# THC-schematicRevE.net
KiCad netlist of a schematic drawn in EAGLE
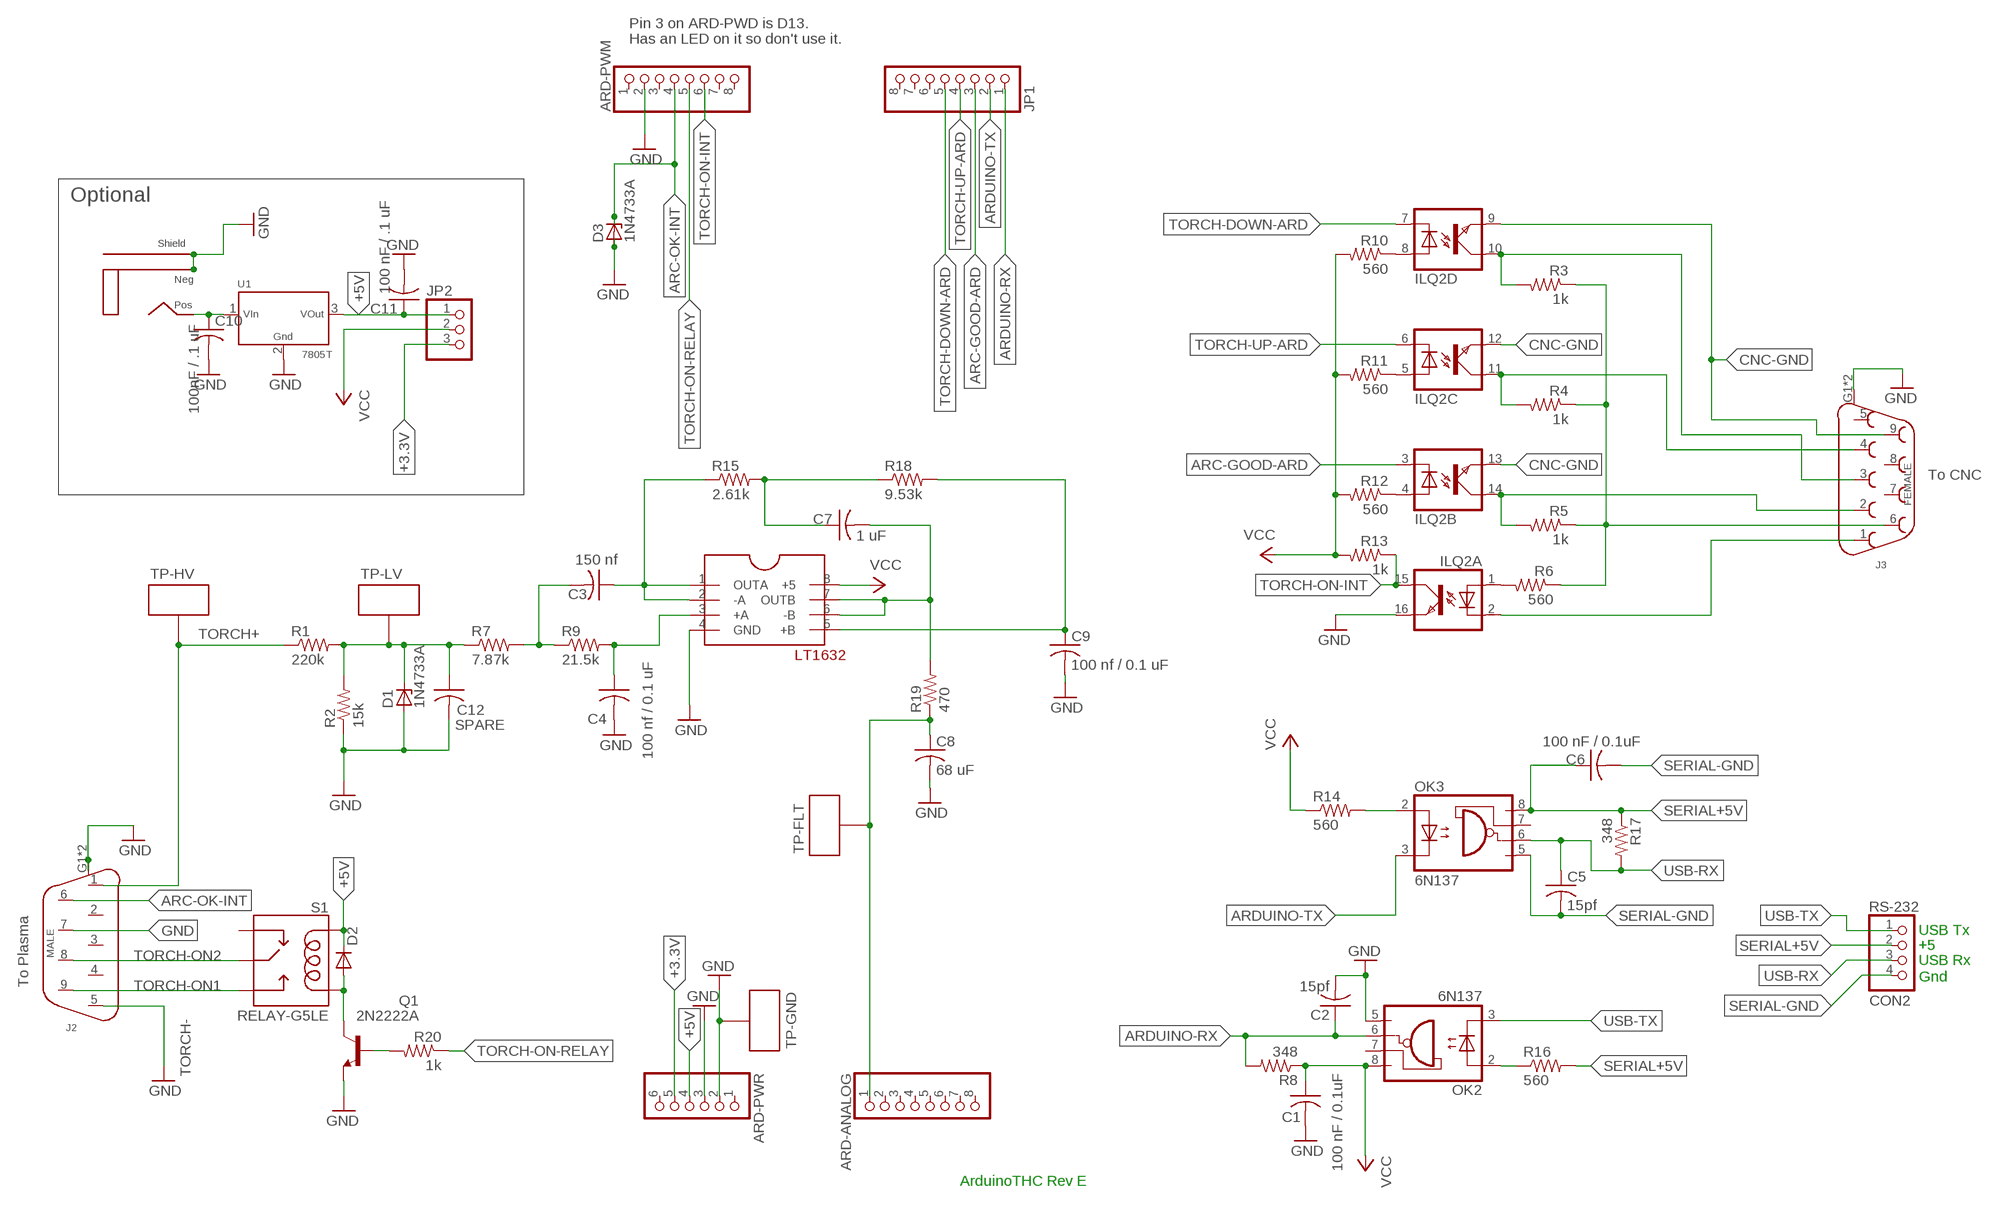
[diagram p0: schematic, sheet 1]

(export (version "E")
  (design (tool "Eeschema 10.0.6"))
  (components
    (comp (ref "ARD-ANALOG")
      (value "PINHD-1X8")
      (footprint "eagle-import:1X08")
      (libsource (lib "eagle-import") (part "PINHD-1X8"))
    )
    (comp (ref "ARD-PWM")
      (value "PINHD-1X8")
      (footprint "eagle-import:1X08")
      (libsource (lib "eagle-import") (part "PINHD-1X8"))
    )
    (comp (ref "ARD-PWR")
      (value "PINHD-1X6")
      (footprint "eagle-import:1X06")
      (libsource (lib "eagle-import") (part "PINHD-1X6"))
    )
    (comp (ref "C1")
      (value "100 nF / 0.1uF")
      (footprint "eagle-import:C025-025X050")
      (libsource (lib "eagle-import") (part "C-US025-025X050"))
    )
    (comp (ref "C2")
      (value "15pf")
      (footprint "eagle-import:C025-025X050")
      (libsource (lib "eagle-import") (part "C-US025-025X050"))
    )
    (comp (ref "C3")
      (value "150 nf")
      (footprint "eagle-import:C025-025X050")
      (libsource (lib "eagle-import") (part "C-US025-025X050"))
    )
    (comp (ref "C4")
      (value "100 nf / 0.1 uF")
      (footprint "eagle-import:C025-025X050")
      (libsource (lib "eagle-import") (part "C-US025-025X050"))
    )
    (comp (ref "C5")
      (value "15pf")
      (footprint "eagle-import:C025-025X050")
      (libsource (lib "eagle-import") (part "C-US025-025X050"))
    )
    (comp (ref "C6")
      (value "100 nF / 0.1uF")
      (footprint "eagle-import:C025-025X050")
      (libsource (lib "eagle-import") (part "C-US025-025X050"))
    )
    (comp (ref "C7")
      (value "1 uF")
      (footprint "eagle-import:C025-025X050")
      (libsource (lib "eagle-import") (part "C-US025-025X050"))
    )
    (comp (ref "C8")
      (value "68 uF")
      (footprint "eagle-import:C025-025X050")
      (libsource (lib "eagle-import") (part "C-US025-025X050"))
    )
    (comp (ref "C9")
      (value "100 nf / 0.1 uF")
      (footprint "eagle-import:C025-025X050")
      (libsource (lib "eagle-import") (part "C-US025-025X050"))
    )
    (comp (ref "C10")
      (value "100nF / .1 uF")
      (footprint "eagle-import:C025-025X050")
      (libsource (lib "eagle-import") (part "C-US025-025X050"))
    )
    (comp (ref "C11")
      (value "100 nF / .1 uF")
      (footprint "eagle-import:C025-025X050")
      (libsource (lib "eagle-import") (part "C-US025-025X050"))
    )
    (comp (ref "C12")
      (value "SPARE")
      (footprint "eagle-import:C025-025X050")
      (libsource (lib "eagle-import") (part "C-US025-025X050"))
    )
    (comp (ref "D1")
      (value "1N4733A")
      (footprint "eagle-import:DO41Z10")
      (libsource (lib "eagle-import") (part "ZPY"))
    )
    (comp (ref "D2")
      (value "1N4001")
      (footprint "eagle-import:DO-204AL")
      (libsource (lib "eagle-import") (part "1N4001"))
    )
    (comp (ref "D3")
      (value "1N4733A")
      (footprint "eagle-import:DO41Z10")
      (libsource (lib "eagle-import") (part "ZPY"))
    )
    (comp (ref "ILQ2")
      (value "ILQ1")
      (footprint "eagle-import:DIL16")
      (fields (field (name "MF") "VISHAY/TELEFUNKEN"))
      (libsource (lib "eagle-import") (part "ILQ1"))
    )
    (comp (ref "J1")
      (value "2.1MM-PLUG-PCB-MNT")
      (footprint "eagle-import:2.1MM-PLUG")
      (libsource (lib "eagle-import") (part "2.1MM-PLUG-PCB-MNT"))
    )
    (comp (ref "J2")
      (value "DB9-MALE")
      (footprint "eagle-import:DB9M-RIGHT-ANGLE")
      (libsource (lib "eagle-import") (part "DB9-MALE"))
    )
    (comp (ref "J3")
      (value "DB9-FEMALE")
      (footprint "eagle-import:DB9F-RIGHT-ANGLE")
      (libsource (lib "eagle-import") (part "DB9-FEMALE"))
    )
    (comp (ref "JP1")
      (value "PINHD-1X8")
      (footprint "eagle-import:1X08")
      (libsource (lib "eagle-import") (part "PINHD-1X8"))
    )
    (comp (ref "JP2")
      (value "PINHD-1X3")
      (footprint "eagle-import:1X03")
      (libsource (lib "eagle-import") (part "PINHD-1X3"))
    )
    (comp (ref "OK2")
      (value "6N137")
      (footprint "eagle-import:DIL08")
      (libsource (lib "eagle-import") (part "6N137"))
    )
    (comp (ref "OK3")
      (value "6N137")
      (footprint "eagle-import:DIL08")
      (libsource (lib "eagle-import") (part "6N137"))
    )
    (comp (ref "Q1")
      (value "2N2222A")
      (footprint "eagle-import:TO18")
      (libsource (lib "eagle-import") (part "2N2222A"))
    )
    (comp (ref "R1")
      (value "220k")
      (footprint "eagle-import:0207_7")
      (libsource (lib "eagle-import") (part "R-US_0207/7"))
    )
    (comp (ref "R2")
      (value "15k")
      (footprint "eagle-import:0207_7")
      (libsource (lib "eagle-import") (part "R-US_0207/7"))
    )
    (comp (ref "R3")
      (value "1k")
      (footprint "eagle-import:0207_7")
      (libsource (lib "eagle-import") (part "R-US_0207/7"))
    )
    (comp (ref "R4")
      (value "1k")
      (footprint "eagle-import:0207_7")
      (libsource (lib "eagle-import") (part "R-US_0207/7"))
    )
    (comp (ref "R5")
      (value "1k")
      (footprint "eagle-import:0207_7")
      (libsource (lib "eagle-import") (part "R-US_0207/7"))
    )
    (comp (ref "R6")
      (value "560")
      (footprint "eagle-import:0207_7")
      (libsource (lib "eagle-import") (part "R-US_0207/7"))
    )
    (comp (ref "R7")
      (value "7.87k")
      (footprint "eagle-import:0207_7")
      (libsource (lib "eagle-import") (part "R-US_0207/7"))
    )
    (comp (ref "R8")
      (value "348")
      (footprint "eagle-import:0207_7")
      (libsource (lib "eagle-import") (part "R-US_0207/7"))
    )
    (comp (ref "R9")
      (value "21.5k")
      (footprint "eagle-import:0207_7")
      (libsource (lib "eagle-import") (part "R-US_0207/7"))
    )
    (comp (ref "R10")
      (value "560")
      (footprint "eagle-import:0207_7")
      (libsource (lib "eagle-import") (part "R-US_0207/7"))
    )
    (comp (ref "R11")
      (value "560")
      (footprint "eagle-import:0207_7")
      (libsource (lib "eagle-import") (part "R-US_0207/7"))
    )
    (comp (ref "R12")
      (value "560")
      (footprint "eagle-import:0207_7")
      (libsource (lib "eagle-import") (part "R-US_0207/7"))
    )
    (comp (ref "R13")
      (value "1k")
      (footprint "eagle-import:0207_7")
      (libsource (lib "eagle-import") (part "R-US_0207/7"))
    )
    (comp (ref "R14")
      (value "560")
      (footprint "eagle-import:0207_7")
      (libsource (lib "eagle-import") (part "R-US_0207/7"))
    )
    (comp (ref "R15")
      (value "2.61k")
      (footprint "eagle-import:0207_7")
      (libsource (lib "eagle-import") (part "R-US_0207/7"))
    )
    (comp (ref "R16")
      (value "560")
      (footprint "eagle-import:0207_7")
      (libsource (lib "eagle-import") (part "R-US_0207/7"))
    )
    (comp (ref "R17")
      (value "348")
      (footprint "eagle-import:0207_7")
      (libsource (lib "eagle-import") (part "R-US_0207/7"))
    )
    (comp (ref "R18")
      (value "9.53k")
      (footprint "eagle-import:0207_7")
      (libsource (lib "eagle-import") (part "R-US_0207/7"))
    )
    (comp (ref "R19")
      (value "470")
      (footprint "eagle-import:0207_7")
      (libsource (lib "eagle-import") (part "R-US_0207/7"))
    )
    (comp (ref "R20")
      (value "1k")
      (footprint "eagle-import:0207_7")
      (libsource (lib "eagle-import") (part "R-US_0207/7"))
    )
    (comp (ref "RS-232")
      (value "CON2")
      (footprint "eagle-import:1X04")
      (libsource (lib "eagle-import") (part "PINHD-1X4"))
    )
    (comp (ref "S1")
      (value "RELAY-G5LE")
      (footprint "eagle-import:RELAY-G5LE")
      (libsource (lib "eagle-import") (part "RELAY-G5LE"))
    )
    (comp (ref "TP-FLT")
      (value "TEST-POINT-.040-HOLE")
      (footprint "eagle-import:TP.040")
      (libsource (lib "eagle-import") (part "TEST-POINT-.040-HOLE"))
    )
    (comp (ref "TP-GND")
      (value "TEST-POINT-.040-HOLE")
      (footprint "eagle-import:TP.040")
      (libsource (lib "eagle-import") (part "TEST-POINT-.040-HOLE"))
    )
    (comp (ref "TP-HV")
      (value "TEST-POINT-.040-HOLE")
      (footprint "eagle-import:TP.040")
      (libsource (lib "eagle-import") (part "TEST-POINT-.040-HOLE"))
    )
    (comp (ref "TP-LV")
      (value "TEST-POINT-.040-HOLE")
      (footprint "eagle-import:TP.040")
      (libsource (lib "eagle-import") (part "TEST-POINT-.040-HOLE"))
    )
    (comp (ref "U$1")
      (value "LT1632")
      (footprint "eagle-import:DIP08")
      (libsource (lib "eagle-import") (part "LT1632"))
    )
    (comp (ref "U1")
      (value "7805T")
      (footprint "eagle-import:TO-220-3")
      (libsource (lib "eagle-import") (part "7805T"))
    )
  )
  (nets
    (net (code "1") (name "+3.3V") (class "Default")
      (node (ref "ARD-PWR") (pin "5") (pinfunction "5_5") (pintype "passive"))
      (node (ref "JP2") (pin "3") (pinfunction "3_3") (pintype "passive"))
    )
    (net (code "2") (name "+5V") (class "Default")
      (node (ref "ARD-PWR") (pin "4") (pinfunction "4_4") (pintype "passive"))
      (node (ref "C11") (pin "1") (pinfunction "1_1") (pintype "passive"))
      (node (ref "D2") (pin "C") (pinfunction "C_C") (pintype "passive"))
      (node (ref "JP2") (pin "1") (pinfunction "1_1") (pintype "passive"))
      (node (ref "S1") (pin "P$5-COIL") (pinfunction "COIL-2_P$5-COIL") (pintype "bidirectional"))
      (node (ref "U1") (pin "3") (pinfunction "VOUT_3") (pintype "bidirectional"))
    )
    (net (code "3") (name "/TORCH-ON1") (class "Default")
      (node (ref "J2") (pin "9") (pinfunction "P$9_9") (pintype "bidirectional"))
      (node (ref "S1") (pin "P$4-NO") (pinfunction "NO_P$4-NO") (pintype "bidirectional"))
    )
    (net (code "4") (name "/TORCH-ON2") (class "Default")
      (node (ref "J2") (pin "8") (pinfunction "P$8_8") (pintype "bidirectional"))
      (node (ref "S1") (pin "P$1-COMMON") (pinfunction "COM_P$1-COMMON") (pintype "bidirectional"))
    )
    (net (code "5") (name "ARC-GOOD-ARD") (class "Default")
      (node (ref "ILQ2") (pin "3") (pinfunction "C_3") (pintype "passive"))
      (node (ref "JP1") (pin "3") (pinfunction "3_3") (pintype "passive"))
    )
    (net (code "6") (name "ARC-OK-INT") (class "Default")
      (node (ref "ARD-PWM") (pin "4") (pinfunction "4_4") (pintype "passive"))
      (node (ref "D3") (pin "C") (pinfunction "C_C") (pintype "passive"))
      (node (ref "J2") (pin "6") (pinfunction "P$6_6") (pintype "bidirectional"))
    )
    (net (code "7") (name "ARDUINO-RX") (class "Default")
      (node (ref "C2") (pin "1") (pinfunction "1_1") (pintype "passive"))
      (node (ref "JP1") (pin "1") (pinfunction "1_1") (pintype "passive"))
      (node (ref "OK2") (pin "6") (pinfunction "VO_6") (pintype "passive"))
      (node (ref "R8") (pin "2") (pinfunction "2_2") (pintype "passive"))
    )
    (net (code "8") (name "ARDUINO-TX") (class "Default")
      (node (ref "JP1") (pin "2") (pinfunction "2_2") (pintype "passive"))
      (node (ref "OK3") (pin "3") (pinfunction "C_3") (pintype "passive"))
    )
    (net (code "9") (name "CNC-GND") (class "Default")
      (node (ref "ILQ2") (pin "12") (pinfunction "EMIT_12") (pintype "passive"))
      (node (ref "ILQ2") (pin "13") (pinfunction "EMIT_13") (pintype "passive"))
      (node (ref "ILQ2") (pin "9") (pinfunction "EMIT_9") (pintype "passive"))
      (node (ref "J3") (pin "9") (pinfunction "P$9_9") (pintype "bidirectional"))
    )
    (net (code "10") (name "GND") (class "Default")
      (node (ref "ARD-PWM") (pin "2") (pinfunction "2_2") (pintype "passive"))
      (node (ref "ARD-PWR") (pin "2") (pinfunction "2_2") (pintype "passive"))
      (node (ref "ARD-PWR") (pin "3") (pinfunction "3_3") (pintype "passive"))
      (node (ref "C1") (pin "2") (pinfunction "2_2") (pintype "passive"))
      (node (ref "C10") (pin "2") (pinfunction "2_2") (pintype "passive"))
      (node (ref "C11") (pin "2") (pinfunction "2_2") (pintype "passive"))
      (node (ref "C12") (pin "2") (pinfunction "2_2") (pintype "passive"))
      (node (ref "C2") (pin "2") (pinfunction "2_2") (pintype "passive"))
      (node (ref "C4") (pin "2") (pinfunction "2_2") (pintype "passive"))
      (node (ref "C8") (pin "2") (pinfunction "2_2") (pintype "passive"))
      (node (ref "C9") (pin "2") (pinfunction "2_2") (pintype "passive"))
      (node (ref "D1") (pin "A") (pinfunction "A_A") (pintype "passive"))
      (node (ref "D3") (pin "A") (pinfunction "A_A") (pintype "passive"))
      (node (ref "ILQ2") (pin "16") (pinfunction "EMIT_16") (pintype "passive"))
      (node (ref "J1") (pin "P$NEG") (pinfunction "P$NEG_P$NEG") (pintype "bidirectional"))
      (node (ref "J1") (pin "P$SHLD") (pinfunction "P$SHLD_P$SHLD") (pintype "bidirectional"))
      (node (ref "J2") (pin "5") (pinfunction "P$5_5") (pintype "bidirectional"))
      (node (ref "J2") (pin "7") (pinfunction "P$7_7") (pintype "bidirectional"))
      (node (ref "J2") (pin "G1") (pinfunction "P$SHLD_G1") (pintype "bidirectional"))
      (node (ref "J2") (pin "G2") (pinfunction "P$SHLD_G2") (pintype "bidirectional"))
      (node (ref "J3") (pin "G1") (pinfunction "P$SHLD_G1") (pintype "bidirectional"))
      (node (ref "J3") (pin "G2") (pinfunction "P$SHLD_G2") (pintype "bidirectional"))
      (node (ref "OK2") (pin "5") (pinfunction "GND_5") (pintype "passive"))
      (node (ref "Q1") (pin "1") (pinfunction "E_1") (pintype "passive"))
      (node (ref "R2") (pin "1") (pinfunction "1_1") (pintype "passive"))
      (node (ref "TP-GND") (pin "P$1") (pinfunction "P$1_P$1") (pintype "bidirectional"))
      (node (ref "U$1") (pin "4") (pinfunction "GND_4") (pintype "bidirectional"))
      (node (ref "U1") (pin "2") (pinfunction "GND_2") (pintype "bidirectional"))
    )
    (net (code "11") (name "Net-(ARD-ANALOG-Pad1)") (class "Default")
      (node (ref "ARD-ANALOG") (pin "1") (pinfunction "1_1") (pintype "passive"))
      (node (ref "C8") (pin "1") (pinfunction "1_1") (pintype "passive"))
      (node (ref "R19") (pin "1") (pinfunction "1_1") (pintype "passive"))
      (node (ref "TP-FLT") (pin "P$1") (pinfunction "P$1_P$1") (pintype "bidirectional"))
    )
    (net (code "12") (name "Net-(C3-Pad2)") (class "Default")
      (node (ref "C3") (pin "2") (pinfunction "2_2") (pintype "passive"))
      (node (ref "R7") (pin "2") (pinfunction "2_2") (pintype "passive"))
      (node (ref "R9") (pin "1") (pinfunction "1_1") (pintype "passive"))
    )
    (net (code "13") (name "Net-(C7-Pad1)") (class "Default")
      (node (ref "C7") (pin "1") (pinfunction "1_1") (pintype "passive"))
      (node (ref "R15") (pin "2") (pinfunction "2_2") (pintype "passive"))
      (node (ref "R18") (pin "1") (pinfunction "1_1") (pintype "passive"))
    )
    (net (code "14") (name "Net-(C12-Pad1)") (class "Default")
      (node (ref "C12") (pin "1") (pinfunction "1_1") (pintype "passive"))
      (node (ref "D1") (pin "C") (pinfunction "C_C") (pintype "passive"))
      (node (ref "R1") (pin "2") (pinfunction "2_2") (pintype "passive"))
      (node (ref "R2") (pin "2") (pinfunction "2_2") (pintype "passive"))
      (node (ref "R7") (pin "1") (pinfunction "1_1") (pintype "passive"))
      (node (ref "TP-LV") (pin "P$1") (pinfunction "P$1_P$1") (pintype "bidirectional"))
    )
    (net (code "15") (name "Net-(ILQ2A-A)") (class "Default")
      (node (ref "ILQ2") (pin "1") (pinfunction "A_1") (pintype "passive"))
      (node (ref "R6") (pin "2") (pinfunction "2_2") (pintype "passive"))
    )
    (net (code "16") (name "Net-(ILQ2A-C)") (class "Default")
      (node (ref "ILQ2") (pin "2") (pinfunction "C_2") (pintype "passive"))
      (node (ref "J3") (pin "1") (pinfunction "P$1_1") (pintype "bidirectional"))
    )
    (net (code "17") (name "Net-(ILQ2B-A)") (class "Default")
      (node (ref "ILQ2") (pin "4") (pinfunction "A_4") (pintype "passive"))
      (node (ref "R12") (pin "1") (pinfunction "1_1") (pintype "passive"))
    )
    (net (code "18") (name "Net-(ILQ2B-COL)") (class "Default")
      (node (ref "ILQ2") (pin "14") (pinfunction "COL_14") (pintype "passive"))
      (node (ref "J3") (pin "2") (pinfunction "P$2_2") (pintype "bidirectional"))
      (node (ref "R5") (pin "2") (pinfunction "2_2") (pintype "passive"))
    )
    (net (code "19") (name "Net-(ILQ2C-A)") (class "Default")
      (node (ref "ILQ2") (pin "5") (pinfunction "A_5") (pintype "passive"))
      (node (ref "R11") (pin "1") (pinfunction "1_1") (pintype "passive"))
    )
    (net (code "20") (name "Net-(ILQ2C-COL)") (class "Default")
      (node (ref "ILQ2") (pin "11") (pinfunction "COL_11") (pintype "passive"))
      (node (ref "J3") (pin "4") (pinfunction "P$4_4") (pintype "bidirectional"))
      (node (ref "R4") (pin "2") (pinfunction "2_2") (pintype "passive"))
    )
    (net (code "21") (name "Net-(ILQ2D-A)") (class "Default")
      (node (ref "ILQ2") (pin "8") (pinfunction "A_8") (pintype "passive"))
      (node (ref "R10") (pin "1") (pinfunction "1_1") (pintype "passive"))
    )
    (net (code "22") (name "Net-(ILQ2D-COL)") (class "Default")
      (node (ref "ILQ2") (pin "10") (pinfunction "COL_10") (pintype "passive"))
      (node (ref "J3") (pin "3") (pinfunction "P$3_3") (pintype "bidirectional"))
      (node (ref "R3") (pin "2") (pinfunction "2_2") (pintype "passive"))
    )
    (net (code "23") (name "Net-(J2-P$1)") (class "Default")
      (node (ref "J2") (pin "1") (pinfunction "P$1_1") (pintype "bidirectional"))
      (node (ref "R1") (pin "1") (pinfunction "1_1") (pintype "passive"))
      (node (ref "TP-HV") (pin "P$1") (pinfunction "P$1_P$1") (pintype "bidirectional"))
    )
    (net (code "24") (name "Net-(J3-P$6)") (class "Default")
      (node (ref "J3") (pin "6") (pinfunction "P$6_6") (pintype "bidirectional"))
      (node (ref "R3") (pin "1") (pinfunction "1_1") (pintype "passive"))
      (node (ref "R4") (pin "1") (pinfunction "1_1") (pintype "passive"))
      (node (ref "R5") (pin "1") (pinfunction "1_1") (pintype "passive"))
      (node (ref "R6") (pin "1") (pinfunction "1_1") (pintype "passive"))
    )
    (net (code "25") (name "Net-(OK2-A)") (class "Default")
      (node (ref "OK2") (pin "2") (pinfunction "A_2") (pintype "passive"))
      (node (ref "R16") (pin "1") (pinfunction "1_1") (pintype "passive"))
    )
    (net (code "26") (name "Net-(OK3-A)") (class "Default")
      (node (ref "OK3") (pin "2") (pinfunction "A_2") (pintype "passive"))
      (node (ref "R14") (pin "2") (pinfunction "2_2") (pintype "passive"))
    )
    (net (code "27") (name "Net-(Q1-B)") (class "Default")
      (node (ref "Q1") (pin "2") (pinfunction "B_2") (pintype "passive"))
      (node (ref "R20") (pin "2") (pinfunction "2_2") (pintype "passive"))
    )
    (net (code "28") (name "Net-(Q1-C)") (class "Default")
      (node (ref "D2") (pin "A") (pinfunction "A_A") (pintype "passive"))
      (node (ref "Q1") (pin "3") (pinfunction "C_3") (pintype "passive"))
      (node (ref "S1") (pin "P$2-COIL") (pinfunction "COIL-1_P$2-COIL") (pintype "bidirectional"))
    )
    (net (code "29") (name "Net-(U$1-+A)") (class "Default")
      (node (ref "C4") (pin "1") (pinfunction "1_1") (pintype "passive"))
      (node (ref "R9") (pin "2") (pinfunction "2_2") (pintype "passive"))
      (node (ref "U$1") (pin "3") (pinfunction "+A_3") (pintype "bidirectional"))
    )
    (net (code "30") (name "Net-(U$1-+B)") (class "Default")
      (node (ref "C9") (pin "1") (pinfunction "1_1") (pintype "passive"))
      (node (ref "R18") (pin "2") (pinfunction "2_2") (pintype "passive"))
      (node (ref "U$1") (pin "5") (pinfunction "+B_5") (pintype "bidirectional"))
    )
    (net (code "31") (name "Net-(U$1--A)") (class "Default")
      (node (ref "C3") (pin "1") (pinfunction "1_1") (pintype "passive"))
      (node (ref "R15") (pin "1") (pinfunction "1_1") (pintype "passive"))
      (node (ref "U$1") (pin "1") (pinfunction "OUTA_1") (pintype "bidirectional"))
      (node (ref "U$1") (pin "2") (pinfunction "-A_2") (pintype "bidirectional"))
    )
    (net (code "32") (name "Net-(U$1--B)") (class "Default")
      (node (ref "C7") (pin "2") (pinfunction "2_2") (pintype "passive"))
      (node (ref "R19") (pin "2") (pinfunction "2_2") (pintype "passive"))
      (node (ref "U$1") (pin "6") (pinfunction "-B_6") (pintype "bidirectional"))
      (node (ref "U$1") (pin "7") (pinfunction "OUTB_7") (pintype "bidirectional"))
    )
    (net (code "33") (name "Net-(U1-VIN)") (class "Default")
      (node (ref "C10") (pin "1") (pinfunction "1_1") (pintype "passive"))
      (node (ref "J1") (pin "P$POS") (pinfunction "P$POS_P$POS") (pintype "bidirectional"))
      (node (ref "U1") (pin "1") (pinfunction "VIN_1") (pintype "bidirectional"))
    )
    (net (code "34") (name "SERIAL+5V") (class "Default")
      (node (ref "C6") (pin "1") (pinfunction "1_1") (pintype "passive"))
      (node (ref "OK3") (pin "8") (pinfunction "VCC_8") (pintype "passive"))
      (node (ref "R16") (pin "2") (pinfunction "2_2") (pintype "passive"))
      (node (ref "R17") (pin "1") (pinfunction "1_1") (pintype "passive"))
      (node (ref "RS-232") (pin "2") (pinfunction "2_2") (pintype "passive"))
    )
    (net (code "35") (name "SERIAL-GND") (class "Default")
      (node (ref "C5") (pin "2") (pinfunction "2_2") (pintype "passive"))
      (node (ref "C6") (pin "2") (pinfunction "2_2") (pintype "passive"))
      (node (ref "OK3") (pin "5") (pinfunction "GND_5") (pintype "passive"))
      (node (ref "RS-232") (pin "4") (pinfunction "4_4") (pintype "passive"))
    )
    (net (code "36") (name "TORCH-DOWN-ARD") (class "Default")
      (node (ref "ILQ2") (pin "7") (pinfunction "C_7") (pintype "passive"))
      (node (ref "JP1") (pin "5") (pinfunction "5_5") (pintype "passive"))
    )
    (net (code "37") (name "TORCH-ON-INT") (class "Default")
      (node (ref "ARD-PWM") (pin "6") (pinfunction "6_6") (pintype "passive"))
      (node (ref "ILQ2") (pin "15") (pinfunction "COL_15") (pintype "passive"))
      (node (ref "R13") (pin "1") (pinfunction "1_1") (pintype "passive"))
    )
    (net (code "38") (name "TORCH-ON-RELAY") (class "Default")
      (node (ref "ARD-PWM") (pin "5") (pinfunction "5_5") (pintype "passive"))
      (node (ref "R20") (pin "1") (pinfunction "1_1") (pintype "passive"))
    )
    (net (code "39") (name "TORCH-UP-ARD") (class "Default")
      (node (ref "ILQ2") (pin "6") (pinfunction "C_6") (pintype "passive"))
      (node (ref "JP1") (pin "4") (pinfunction "4_4") (pintype "passive"))
    )
    (net (code "40") (name "USB-RX") (class "Default")
      (node (ref "C5") (pin "1") (pinfunction "1_1") (pintype "passive"))
      (node (ref "OK3") (pin "6") (pinfunction "VO_6") (pintype "passive"))
      (node (ref "R17") (pin "2") (pinfunction "2_2") (pintype "passive"))
      (node (ref "RS-232") (pin "3") (pinfunction "3_3") (pintype "passive"))
    )
    (net (code "41") (name "USB-TX") (class "Default")
      (node (ref "OK2") (pin "3") (pinfunction "C_3") (pintype "passive"))
      (node (ref "RS-232") (pin "1") (pinfunction "1_1") (pintype "passive"))
    )
    (net (code "42") (name "VCC") (class "Default")
      (node (ref "C1") (pin "1") (pinfunction "1_1") (pintype "passive"))
      (node (ref "JP2") (pin "2") (pinfunction "2_2") (pintype "passive"))
      (node (ref "OK2") (pin "8") (pinfunction "VCC_8") (pintype "passive"))
      (node (ref "R10") (pin "2") (pinfunction "2_2") (pintype "passive"))
      (node (ref "R11") (pin "2") (pinfunction "2_2") (pintype "passive"))
      (node (ref "R12") (pin "2") (pinfunction "2_2") (pintype "passive"))
      (node (ref "R13") (pin "2") (pinfunction "2_2") (pintype "passive"))
      (node (ref "R14") (pin "1") (pinfunction "1_1") (pintype "passive"))
      (node (ref "R8") (pin "1") (pinfunction "1_1") (pintype "passive"))
      (node (ref "U$1") (pin "8") (pinfunction "+5_8") (pintype "bidirectional"))
    )
    (net (code "43") (name "unconnected-(ARD-ANALOG-Pad2)") (class "Default")
      (node (ref "ARD-ANALOG") (pin "2") (pinfunction "2_2") (pintype "passive"))
    )
    (net (code "44") (name "unconnected-(ARD-ANALOG-Pad3)") (class "Default")
      (node (ref "ARD-ANALOG") (pin "3") (pinfunction "3_3") (pintype "passive"))
    )
    (net (code "45") (name "unconnected-(ARD-ANALOG-Pad4)") (class "Default")
      (node (ref "ARD-ANALOG") (pin "4") (pinfunction "4_4") (pintype "passive"))
    )
    (net (code "46") (name "unconnected-(ARD-ANALOG-Pad5)") (class "Default")
      (node (ref "ARD-ANALOG") (pin "5") (pinfunction "5_5") (pintype "passive"))
    )
    (net (code "47") (name "unconnected-(ARD-ANALOG-Pad6)") (class "Default")
      (node (ref "ARD-ANALOG") (pin "6") (pinfunction "6_6") (pintype "passive"))
    )
    (net (code "48") (name "unconnected-(ARD-ANALOG-Pad7)") (class "Default")
      (node (ref "ARD-ANALOG") (pin "7") (pinfunction "7_7") (pintype "passive"))
    )
    (net (code "49") (name "unconnected-(ARD-ANALOG-Pad8)") (class "Default")
      (node (ref "ARD-ANALOG") (pin "8") (pinfunction "8_8") (pintype "passive"))
    )
    (net (code "50") (name "unconnected-(ARD-PWM-Pad1)") (class "Default")
      (node (ref "ARD-PWM") (pin "1") (pinfunction "1_1") (pintype "passive"))
    )
    (net (code "51") (name "unconnected-(ARD-PWM-Pad3)") (class "Default")
      (node (ref "ARD-PWM") (pin "3") (pinfunction "3_3") (pintype "passive"))
    )
    (net (code "52") (name "unconnected-(ARD-PWM-Pad7)") (class "Default")
      (node (ref "ARD-PWM") (pin "7") (pinfunction "7_7") (pintype "passive"))
    )
    (net (code "53") (name "unconnected-(ARD-PWM-Pad8)") (class "Default")
      (node (ref "ARD-PWM") (pin "8") (pinfunction "8_8") (pintype "passive"))
    )
    (net (code "54") (name "unconnected-(ARD-PWR-Pad1)") (class "Default")
      (node (ref "ARD-PWR") (pin "1") (pinfunction "1_1") (pintype "passive"))
    )
    (net (code "55") (name "unconnected-(ARD-PWR-Pad6)") (class "Default")
      (node (ref "ARD-PWR") (pin "6") (pinfunction "6_6") (pintype "passive"))
    )
    (net (code "56") (name "unconnected-(J2-P$2-Pad2)") (class "Default")
      (node (ref "J2") (pin "2") (pinfunction "P$2_2") (pintype "bidirectional"))
    )
    (net (code "57") (name "unconnected-(J2-P$3-Pad3)") (class "Default")
      (node (ref "J2") (pin "3") (pinfunction "P$3_3") (pintype "bidirectional"))
    )
    (net (code "58") (name "unconnected-(J2-P$4-Pad4)") (class "Default")
      (node (ref "J2") (pin "4") (pinfunction "P$4_4") (pintype "bidirectional"))
    )
    (net (code "59") (name "unconnected-(J3-P$5-Pad5)") (class "Default")
      (node (ref "J3") (pin "5") (pinfunction "P$5_5") (pintype "bidirectional"))
    )
    (net (code "60") (name "unconnected-(J3-P$7-Pad7)") (class "Default")
      (node (ref "J3") (pin "7") (pinfunction "P$7_7") (pintype "bidirectional"))
    )
    (net (code "61") (name "unconnected-(J3-P$8-Pad8)") (class "Default")
      (node (ref "J3") (pin "8") (pinfunction "P$8_8") (pintype "bidirectional"))
    )
    (net (code "62") (name "unconnected-(JP1-Pad6)") (class "Default")
      (node (ref "JP1") (pin "6") (pinfunction "6_6") (pintype "passive"))
    )
    (net (code "63") (name "unconnected-(JP1-Pad7)") (class "Default")
      (node (ref "JP1") (pin "7") (pinfunction "7_7") (pintype "passive"))
    )
    (net (code "64") (name "unconnected-(JP1-Pad8)") (class "Default")
      (node (ref "JP1") (pin "8") (pinfunction "8_8") (pintype "passive"))
    )
    (net (code "65") (name "unconnected-(OK2-VE-Pad7)") (class "Default")
      (node (ref "OK2") (pin "7") (pinfunction "VE_7") (pintype "passive"))
    )
    (net (code "66") (name "unconnected-(OK3-VE-Pad7)") (class "Default")
      (node (ref "OK3") (pin "7") (pinfunction "VE_7") (pintype "passive"))
    )
    (net (code "67") (name "unconnected-(S1-NC-PadP$3-NC)") (class "Default")
      (node (ref "S1") (pin "P$3-NC") (pinfunction "NC_P$3-NC") (pintype "bidirectional"))
    )
  )
)
